# Controller_R2.net
KiCad netlist of a schematic drawn in Altium Designer
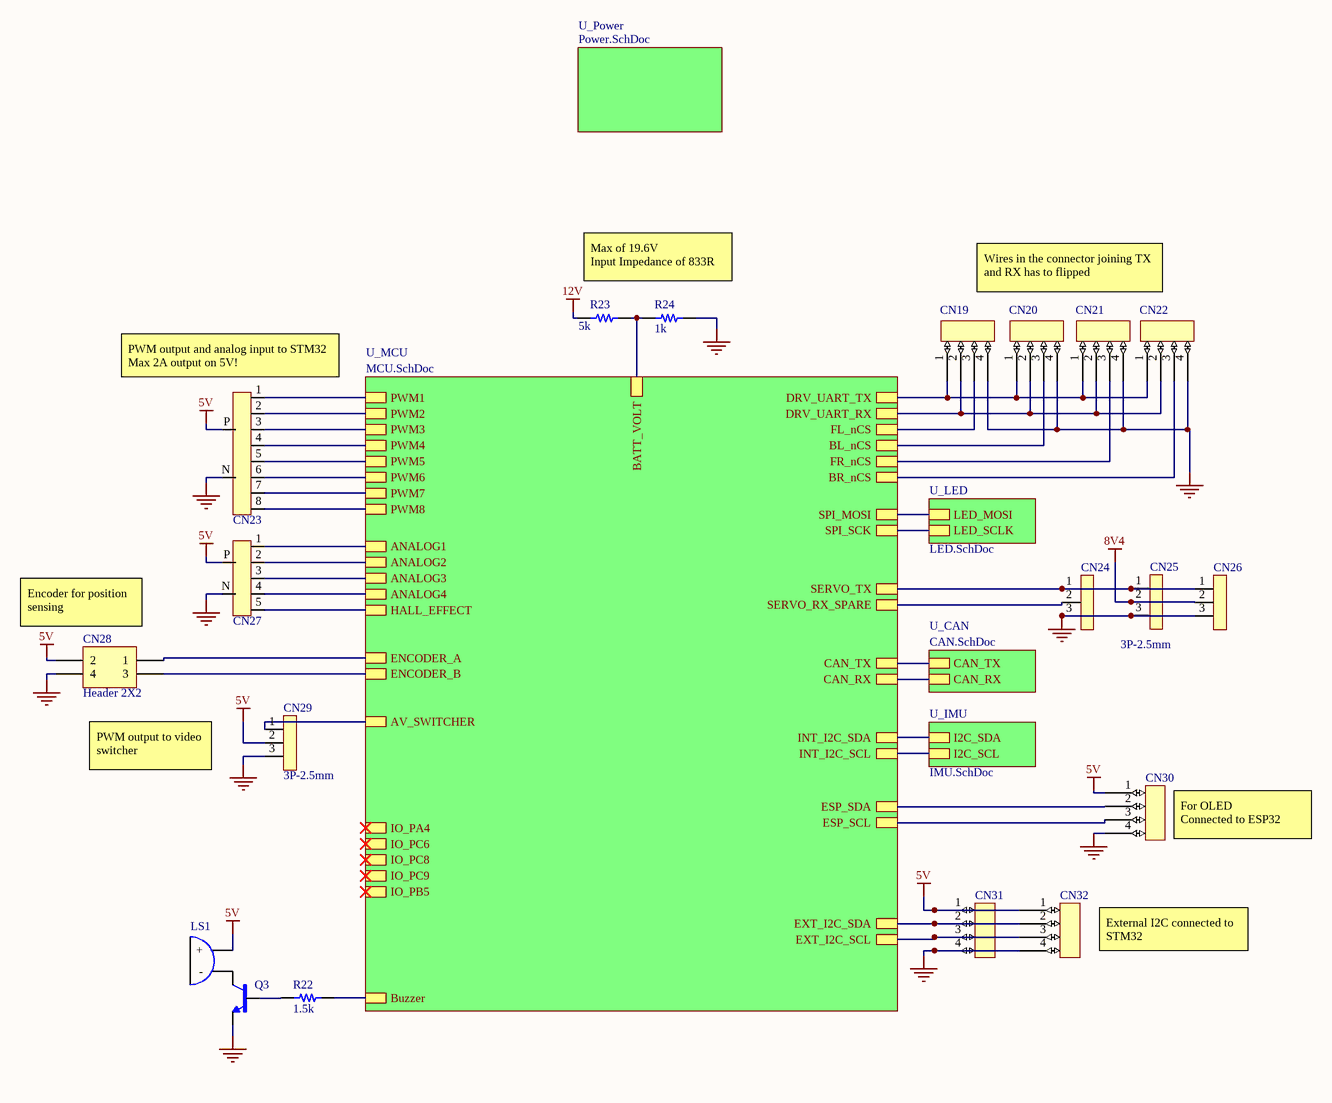
[diagram p0: Controller R2.SchDoc]

(export (version "E")
  (design (tool "Eeschema 10.0.6"))
  (components
    (comp (ref "CN19") (value "JST_GH-4P") (footprint "JST_GH-4P") (libsource (lib "") (part "JST_GH-4P_1")))
    (comp (ref "CN20") (value "JST_GH-4P") (footprint "JST_GH-4P") (libsource (lib "") (part "JST_GH-4P_1")))
    (comp (ref "CN21") (value "JST_GH-4P") (footprint "JST_GH-4P") (libsource (lib "") (part "JST_GH-4P_1")))
    (comp (ref "CN22") (value "JST_GH-4P") (footprint "JST_GH-4P") (libsource (lib "") (part "JST_GH-4P_1")))
    (comp (ref "CN23")
      (value "8P-Signal-2.5mm")
      (footprint "8ch-signal-header")
      (libsource (lib "Parts") (part "8P-Signal-2.5mm"))
    )
    (comp (ref "CN24") (value "3P-2.5mm") (footprint "2.5mm-3P") (libsource (lib "Parts") (part "3P-2.5mm")))
    (comp (ref "CN25") (value "3P-2.5mm") (footprint "2.5mm-3P") (libsource (lib "Parts") (part "3P-2.5mm")))
    (comp (ref "CN26") (value "3P-2.5mm") (footprint "2.5mm-3P") (libsource (lib "Parts") (part "3P-2.5mm")))
    (comp (ref "CN27")
      (value "5P-Signal-2.5mm")
      (footprint "5ch-signal-header")
      (libsource (lib "Parts") (part "5P-Signal-2.5mm"))
    )
    (comp (ref "CN28")
      (value "Header 2X2")
      (footprint "HDR2X2")
      (description "Header, 2-Pin, Dual row")
      (fields (field (name "PUBLISHER") "Altium Limited"))
      (libsource (lib "Miscellaneous Connectors") (part "Header 2X2"))
    )
    (comp (ref "CN29") (value "3P-2.5mm") (footprint "2.5mm-3P") (libsource (lib "Parts") (part "3P-2.5mm")))
    (comp (ref "CN30")
      (value "JST_GH-4P")
      (footprint "JST_GH-4P")
      (libsource (lib "Parts") (part "JST_GH-4P"))
    )
    (comp (ref "CN31")
      (value "JST_GH-4P")
      (footprint "JST_GH-4P")
      (libsource (lib "Parts") (part "JST_GH-4P"))
    )
    (comp (ref "CN32")
      (value "JST_GH-4P")
      (footprint "JST_GH-4P")
      (libsource (lib "Parts") (part "JST_GH-4P"))
    )
    (comp (ref "LS1") (value "Buzzer") (footprint "12-dia-buzzer") (libsource (lib "Parts") (part "Buzzer")))
    (comp (ref "Q3")
      (value "S8050")
      (footprint "SOT23-FET")
      (fields
        (field (name "MF") "MICROSS/On Semiconductor")
        (field (name "DIGI-KEY_PART_NUMBER") "1086-15156-ND")
        (field (name "MP") "2N2222")
      )
      (libsource (lib "Parts") (part "S8050"))
    )
    (comp (ref "R22")
      (value "1.5k")
      (footprint "0805 - duplicate")
      (libsource (lib "Parts") (part "Resistor"))
    )
    (comp (ref "R23") (value "5k") (footprint "0805 - duplicate") (libsource (lib "Parts") (part "Resistor")))
    (comp (ref "R24") (value "1k") (footprint "0805 - duplicate") (libsource (lib "Parts") (part "Resistor")))
  )
  (nets
    (net (code "1") (name "/ANALOG1") (class "Default") (node (ref "CN27") (pin "1") (pintype "passive")))
    (net (code "2") (name "/ANALOG2") (class "Default") (node (ref "CN27") (pin "2") (pintype "passive")))
    (net (code "3") (name "/ANALOG3") (class "Default") (node (ref "CN27") (pin "3") (pintype "passive")))
    (net (code "4") (name "/ANALOG4") (class "Default") (node (ref "CN27") (pin "4") (pintype "passive")))
    (net (code "5") (name "/AV_SWITCHER") (class "Default") (node (ref "CN29") (pin "1") (pintype "passive")))
    (net (code "6") (name "/BATT_VOLT") (class "Default")
      (node (ref "R23") (pin "2") (pinfunction "2_2") (pintype "passive"))
      (node (ref "R24") (pin "1") (pinfunction "1_1") (pintype "passive"))
    )
    (net (code "7") (name "/BL_nCS") (class "Default")
      (node (ref "CN20") (pin "3") (pintype "bidirectional"))
    )
    (net (code "8") (name "/BR_nCS") (class "Default")
      (node (ref "CN22") (pin "3") (pintype "bidirectional"))
    )
    (net (code "9") (name "/Buzzer") (class "Default")
      (node (ref "R22") (pin "2") (pinfunction "2_2") (pintype "passive"))
    )
    (net (code "12") (name "/DRV_UART_RX") (class "Default")
      (node (ref "CN19") (pin "2") (pintype "bidirectional"))
      (node (ref "CN20") (pin "2") (pintype "bidirectional"))
      (node (ref "CN21") (pin "2") (pintype "bidirectional"))
      (node (ref "CN22") (pin "2") (pintype "bidirectional"))
    )
    (net (code "13") (name "/DRV_UART_TX") (class "Default")
      (node (ref "CN19") (pin "1") (pintype "bidirectional"))
      (node (ref "CN20") (pin "1") (pintype "bidirectional"))
      (node (ref "CN21") (pin "1") (pintype "bidirectional"))
      (node (ref "CN22") (pin "1") (pintype "bidirectional"))
    )
    (net (code "14") (name "/ENCODER_A") (class "Default")
      (node (ref "CN28") (pin "1") (pinfunction "1_1") (pintype "passive"))
    )
    (net (code "15") (name "/ENCODER_B") (class "Default")
      (node (ref "CN28") (pin "3") (pinfunction "3_3") (pintype "passive"))
    )
    (net (code "16") (name "/ESP_SCL") (class "Default")
      (node (ref "CN30") (pin "3") (pintype "bidirectional"))
    )
    (net (code "17") (name "/ESP_SDA") (class "Default")
      (node (ref "CN30") (pin "2") (pintype "bidirectional"))
    )
    (net (code "18") (name "/EXT_I2C_SCL") (class "Default")
      (node (ref "CN31") (pin "3") (pintype "bidirectional"))
      (node (ref "CN32") (pin "3") (pintype "bidirectional"))
    )
    (net (code "19") (name "/EXT_I2C_SDA") (class "Default")
      (node (ref "CN31") (pin "2") (pintype "bidirectional"))
      (node (ref "CN32") (pin "2") (pintype "bidirectional"))
    )
    (net (code "20") (name "/FL_nCS") (class "Default")
      (node (ref "CN19") (pin "3") (pintype "bidirectional"))
    )
    (net (code "21") (name "/FR_nCS") (class "Default")
      (node (ref "CN21") (pin "3") (pintype "bidirectional"))
    )
    (net (code "22") (name "/HALL_EFFECT") (class "Default")
      (node (ref "CN27") (pin "5") (pintype "passive"))
    )
    (net (code "32") (name "/PWM1") (class "Default") (node (ref "CN23") (pin "1") (pintype "passive")))
    (net (code "33") (name "/PWM2") (class "Default") (node (ref "CN23") (pin "2") (pintype "passive")))
    (net (code "34") (name "/PWM3") (class "Default") (node (ref "CN23") (pin "3") (pintype "passive")))
    (net (code "35") (name "/PWM4") (class "Default") (node (ref "CN23") (pin "4") (pintype "passive")))
    (net (code "36") (name "/PWM5") (class "Default") (node (ref "CN23") (pin "5") (pintype "passive")))
    (net (code "37") (name "/PWM6") (class "Default") (node (ref "CN23") (pin "6") (pintype "passive")))
    (net (code "38") (name "/PWM7") (class "Default") (node (ref "CN23") (pin "7") (pintype "passive")))
    (net (code "39") (name "/PWM8") (class "Default") (node (ref "CN23") (pin "8") (pintype "passive")))
    (net (code "40") (name "/SERVO_RX_SPARE") (class "Default")
      (node (ref "CN24") (pin "2") (pintype "passive"))
    )
    (net (code "41") (name "/SERVO_TX") (class "Default")
      (node (ref "CN24") (pin "1") (pintype "passive"))
      (node (ref "CN25") (pin "1") (pintype "passive"))
      (node (ref "CN26") (pin "1") (pintype "passive"))
    )
    (net (code "42") (name "5V") (class "Default")
      (node (ref "CN23") (pin "P") (pintype "passive"))
      (node (ref "CN27") (pin "P") (pintype "passive"))
      (node (ref "CN28") (pin "2") (pinfunction "2_2") (pintype "passive"))
      (node (ref "CN29") (pin "2") (pintype "passive"))
      (node (ref "CN30") (pin "1") (pintype "bidirectional"))
      (node (ref "CN31") (pin "1") (pintype "bidirectional"))
      (node (ref "CN32") (pin "1") (pintype "bidirectional"))
      (node (ref "LS1") (pin "A") (pinfunction "+_A") (pintype "passive"))
    )
    (net (code "43") (name "8V4") (class "Default")
      (node (ref "CN25") (pin "2") (pintype "passive"))
      (node (ref "CN26") (pin "2") (pintype "passive"))
    )
    (net (code "44") (name "12V") (class "Default")
      (node (ref "R23") (pin "1") (pinfunction "1_1") (pintype "passive"))
    )
    (net (code "45") (name "GND") (class "Default")
      (node (ref "CN19") (pin "4") (pintype "bidirectional"))
      (node (ref "CN20") (pin "4") (pintype "bidirectional"))
      (node (ref "CN21") (pin "4") (pintype "bidirectional"))
      (node (ref "CN22") (pin "4") (pintype "bidirectional"))
      (node (ref "CN23") (pin "N") (pintype "passive"))
      (node (ref "CN24") (pin "3") (pintype "passive"))
      (node (ref "CN25") (pin "3") (pintype "passive"))
      (node (ref "CN26") (pin "3") (pintype "passive"))
      (node (ref "CN27") (pin "N") (pintype "passive"))
      (node (ref "CN28") (pin "4") (pinfunction "4_4") (pintype "passive"))
      (node (ref "CN29") (pin "3") (pintype "passive"))
      (node (ref "CN30") (pin "4") (pintype "bidirectional"))
      (node (ref "CN31") (pin "4") (pintype "bidirectional"))
      (node (ref "CN32") (pin "4") (pintype "bidirectional"))
      (node (ref "Q3") (pin "2") (pinfunction "E_2") (pintype "passive"))
      (node (ref "R24") (pin "2") (pinfunction "2_2") (pintype "passive"))
    )
    (net (code "46") (name "Net-(LS1--)") (class "Default")
      (node (ref "LS1") (pin "K") (pinfunction "-_K") (pintype "passive"))
      (node (ref "Q3") (pin "3") (pinfunction "C_3") (pintype "passive"))
    )
    (net (code "47") (name "Net-(Q3-B)") (class "Default")
      (node (ref "Q3") (pin "1") (pinfunction "B_1") (pintype "passive"))
      (node (ref "R22") (pin "1") (pinfunction "1_1") (pintype "passive"))
    )
  )
)
